# Shark.net
KiCad netlist of a schematic drawn in Altium Designer
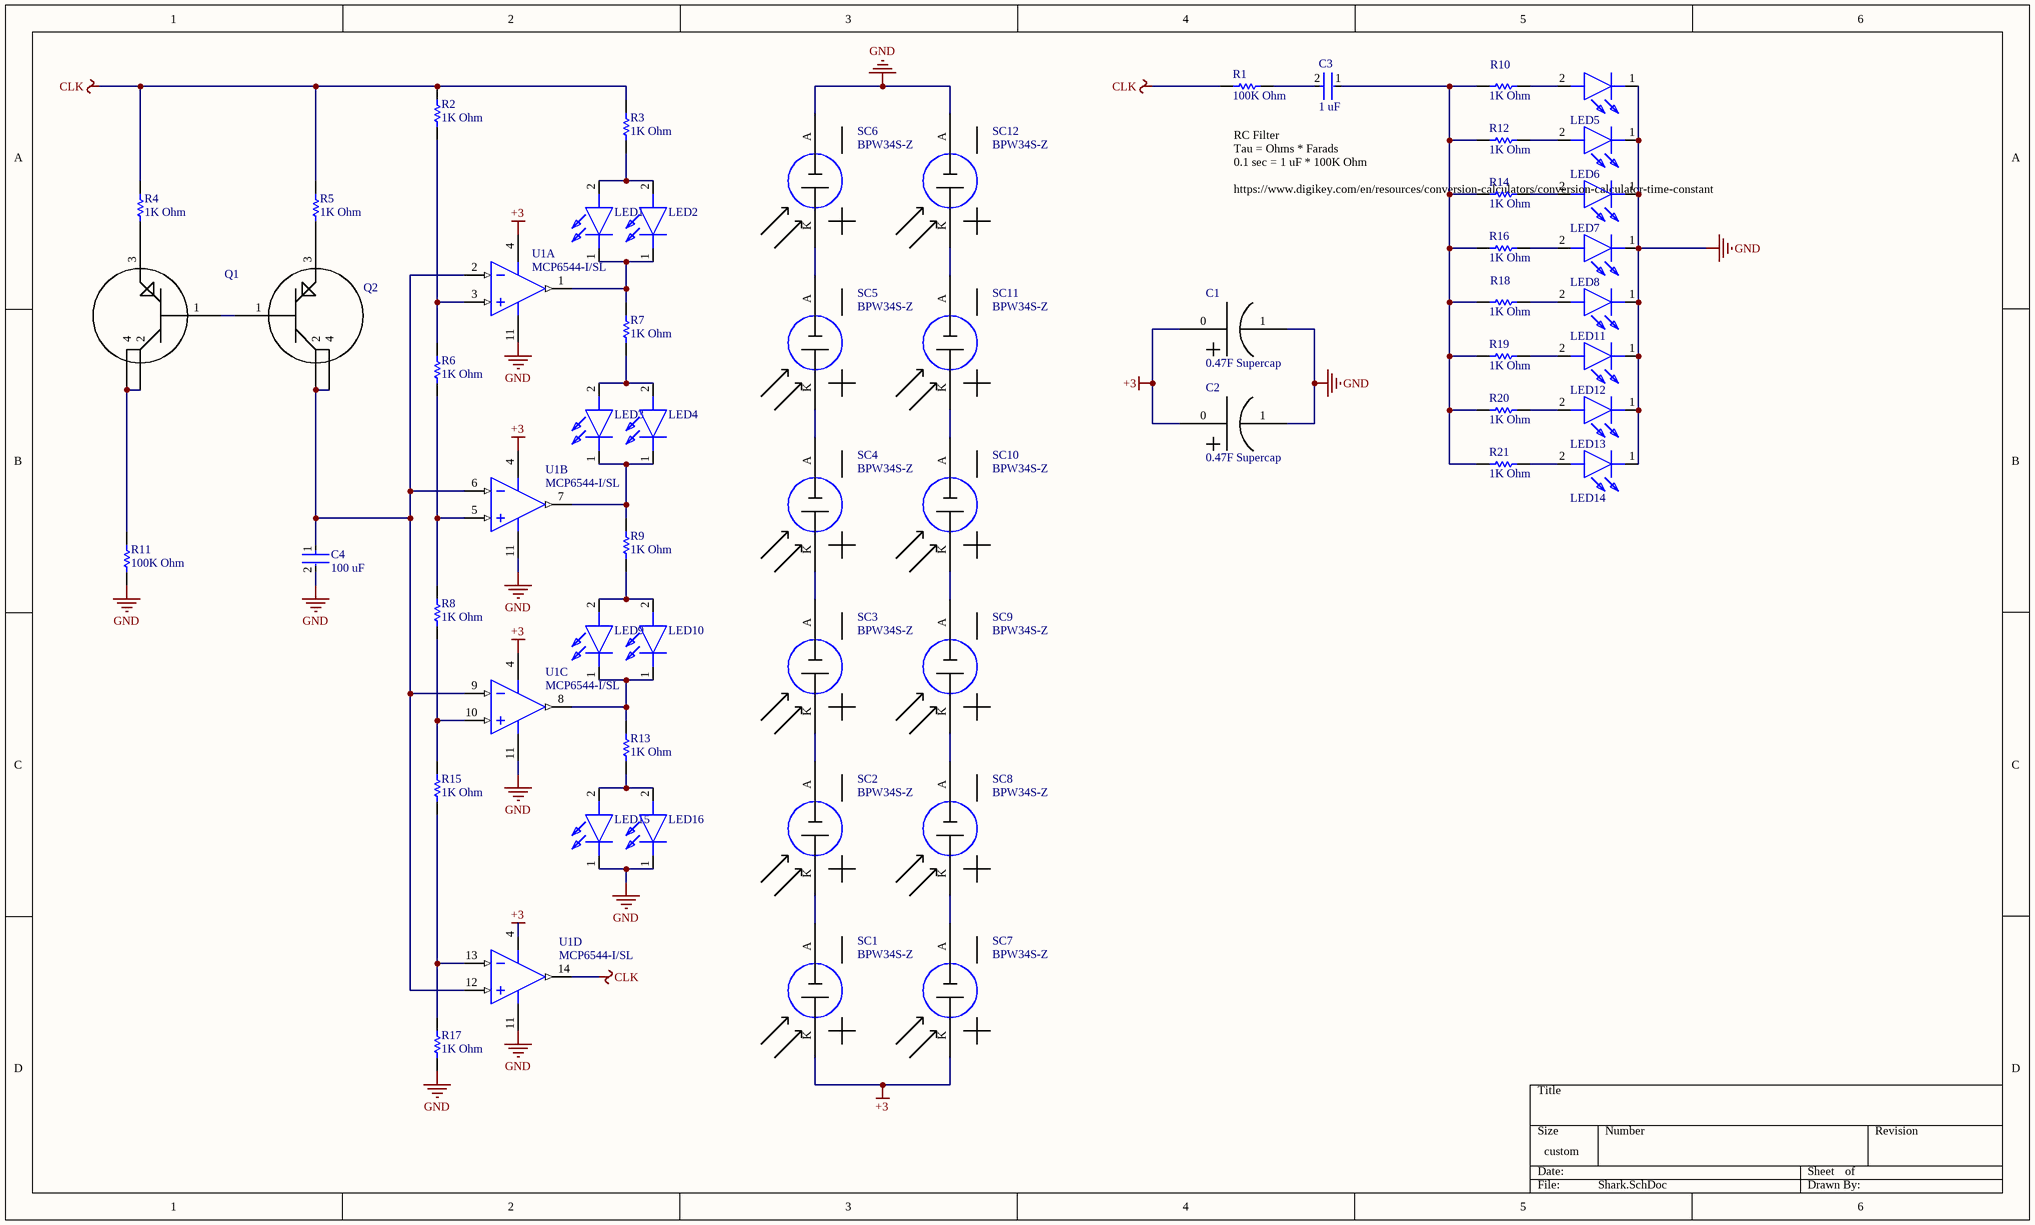
[diagram p0: Shark.SchDoc]

(export (version "E")
  (design (tool "Eeschema 10.0.6"))
  (components
    (comp (ref "C1")
      (value "0.47F Supercap")
      (footprint "JUMT1474MED")
      (description "Cap Supercap 0.47F 2.7V 20% (6.3 X 9mm) Radial 2.5mm 4 Ohm 1000h 70C Bulk Automotive")
      (fields
        (field (name "MANUFACTURER") "Nichicon")
        (field (name "MANUFACTURER PART NUMBER") "JUMT1474MED")
      )
      (libsource (lib "Schlib1") (part "JUMT1474MED"))
    )
    (comp (ref "C2")
      (value "0.47F Supercap")
      (footprint "JUMT1474MED")
      (description "Cap Supercap 0.47F 2.7V 20% (6.3 X 9mm) Radial 2.5mm 4 Ohm 1000h 70C Bulk Automotive")
      (fields
        (field (name "MANUFACTURER") "Nichicon")
        (field (name "MANUFACTURER PART NUMBER") "JUMT1474MED")
      )
      (libsource (lib "Schlib1") (part "JUMT1474MED"))
    )
    (comp (ref "C3")
      (value "1 uF")
      (footprint "FP-1812-L_4_5_0_3-W_3_2_0-IPC_B")
      (description "General Purpose Ceramic Capacitor, 1812, 1uF, 10%, X7R, 15%, 100V")
      (fields (field (name "TOLERANCE") "10%") (field (name "VOLTAGE") "100V"))
      (libsource (lib "Altium Content Vault") (part "f23184f103b6ebe33a8c269c53dcba6"))
    )
    (comp (ref "C4")
      (value "100 uF")
      (footprint "FP-GRM21B-0_2-e0_2_0_7-IPC_A")
      (description "Chip Multilayer Ceramic Capacitors for General Purpose, 0805, 100uF, X5R, 15%, 20%, 6.3V")
      (fields (field (name "TOLERANCE") "20%"))
      (libsource (lib "Altium Content Vault") (part "b4654b650e69147ec39a6b967a45e02"))
    )
    (comp (ref "LED1")
      (value "CSL1104WBBW1")
      (footprint "CSL1104WBBW1")
      (description "LED")
      (libsource (lib "Schlib1") (part "CSL1104WBBW1"))
    )
    (comp (ref "LED2")
      (value "CSL1104WBBW1")
      (footprint "CSL1104WBBW1")
      (description "LED")
      (libsource (lib "Schlib1") (part "CSL1104WBBW1"))
    )
    (comp (ref "LED3")
      (value "CSL1104WBBW1")
      (footprint "CSL1104WBBW1")
      (description "LED")
      (libsource (lib "Schlib1") (part "CSL1104WBBW1"))
    )
    (comp (ref "LED4")
      (value "CSL1104WBBW1")
      (footprint "CSL1104WBBW1")
      (description "LED")
      (libsource (lib "Schlib1") (part "CSL1104WBBW1"))
    )
    (comp (ref "LED5")
      (value "CSL1104WBBW1")
      (footprint "CSL1104WBBW1")
      (description "LED")
      (libsource (lib "Schlib1") (part "CSL1104WBBW1"))
    )
    (comp (ref "LED6")
      (value "CSL1104WBBW1")
      (footprint "CSL1104WBBW1")
      (description "LED")
      (libsource (lib "Schlib1") (part "CSL1104WBBW1"))
    )
    (comp (ref "LED7")
      (value "CSL1104WBBW1")
      (footprint "CSL1104WBBW1")
      (description "LED")
      (libsource (lib "Schlib1") (part "CSL1104WBBW1"))
    )
    (comp (ref "LED8")
      (value "CSL1104WBBW1")
      (footprint "CSL1104WBBW1")
      (description "LED")
      (libsource (lib "Schlib1") (part "CSL1104WBBW1"))
    )
    (comp (ref "LED9")
      (value "CSL1104WBBW1")
      (footprint "CSL1104WBBW1")
      (description "LED")
      (libsource (lib "Schlib1") (part "CSL1104WBBW1"))
    )
    (comp (ref "LED10")
      (value "CSL1104WBBW1")
      (footprint "CSL1104WBBW1")
      (description "LED")
      (libsource (lib "Schlib1") (part "CSL1104WBBW1"))
    )
    (comp (ref "LED11")
      (value "CSL1104WBBW1")
      (footprint "CSL1104WBBW1")
      (description "LED")
      (libsource (lib "Schlib1") (part "CSL1104WBBW1"))
    )
    (comp (ref "LED12")
      (value "CSL1104WBBW1")
      (footprint "CSL1104WBBW1")
      (description "LED")
      (libsource (lib "Schlib1") (part "CSL1104WBBW1"))
    )
    (comp (ref "LED13")
      (value "CSL1104WBBW1")
      (footprint "CSL1104WBBW1")
      (description "LED")
      (libsource (lib "Schlib1") (part "CSL1104WBBW1"))
    )
    (comp (ref "LED14")
      (value "CSL1104WBBW1")
      (footprint "CSL1104WBBW1")
      (description "LED")
      (libsource (lib "Schlib1") (part "CSL1104WBBW1"))
    )
    (comp (ref "LED15")
      (value "CSL1104WBBW1")
      (footprint "CSL1104WBBW1")
      (description "LED")
      (libsource (lib "Schlib1") (part "CSL1104WBBW1"))
    )
    (comp (ref "LED16")
      (value "CSL1104WBBW1")
      (footprint "CSL1104WBBW1")
      (description "LED")
      (libsource (lib "Schlib1") (part "CSL1104WBBW1"))
    )
    (comp (ref "Q1")
      (value "PZT3906T1G")
      (footprint "PZT3906T1G")
      (description "Transistor Gp Bjt PNP 40V 200MA 4-PIN SOT-223 T/r")
      (fields (field (name "MANUFACTURER") "ON Semiconductor"))
      (libsource (lib "Schlib1") (part "PZT3906T1G"))
    )
    (comp (ref "Q2")
      (value "PZT3906T1G")
      (footprint "PZT3906T1G")
      (description "Transistor Gp Bjt PNP 40V 200MA 4-PIN SOT-223 T/r")
      (fields (field (name "MANUFACTURER") "ON Semiconductor"))
      (libsource (lib "Schlib1") (part "PZT3906T1G"))
    )
    (comp (ref "R1")
      (value "100K Ohm")
      (footprint "RESC2013X60X35ML10T20")
      (description "Chip Resistor, 100 KOhm, +/- 1%, 0.125 W, -55 to 155 degC, 0805 (2012 Metric), RoHS, Tape and Reel")
      (fields (field (name "MANUFACTURER") "Yageo") (field (name "TOLERANCE") "1%"))
      (libsource (lib "Altium Content Vault") (part "RES-2"))
    )
    (comp (ref "R2")
      (value "1K Ohm")
      (footprint "RESC2013X50X30NL20T20")
      (fields (field (name "PART NUMBER") "CRCW08051K00FKEA") (field (name "MANUFACTURER") "Vishay Dale"))
      (libsource (lib "Altium Content Vault") (part "RES"))
    )
    (comp (ref "R3")
      (value "1K Ohm")
      (footprint "RESC2013X50X30NL20T20")
      (fields (field (name "PART NUMBER") "CRCW08051K00FKEA") (field (name "MANUFACTURER") "Vishay Dale"))
      (libsource (lib "Altium Content Vault") (part "RES"))
    )
    (comp (ref "R4")
      (value "1K Ohm")
      (footprint "RESC2013X50X30NL20T20")
      (fields (field (name "PART NUMBER") "CRCW08051K00FKEA") (field (name "MANUFACTURER") "Vishay Dale"))
      (libsource (lib "Altium Content Vault") (part "RES"))
    )
    (comp (ref "R5")
      (value "1K Ohm")
      (footprint "RESC2013X50X30NL20T20")
      (fields (field (name "PART NUMBER") "CRCW08051K00FKEA") (field (name "MANUFACTURER") "Vishay Dale"))
      (libsource (lib "Altium Content Vault") (part "RES"))
    )
    (comp (ref "R6")
      (value "1K Ohm")
      (footprint "RESC2013X50X30NL20T20")
      (fields (field (name "PART NUMBER") "CRCW08051K00FKEA") (field (name "MANUFACTURER") "Vishay Dale"))
      (libsource (lib "Altium Content Vault") (part "RES"))
    )
    (comp (ref "R7")
      (value "1K Ohm")
      (footprint "RESC2013X50X30NL20T20")
      (fields (field (name "PART NUMBER") "CRCW08051K00FKEA") (field (name "MANUFACTURER") "Vishay Dale"))
      (libsource (lib "Altium Content Vault") (part "RES"))
    )
    (comp (ref "R8")
      (value "1K Ohm")
      (footprint "RESC2013X50X30NL20T20")
      (fields (field (name "PART NUMBER") "CRCW08051K00FKEA") (field (name "MANUFACTURER") "Vishay Dale"))
      (libsource (lib "Altium Content Vault") (part "RES"))
    )
    (comp (ref "R9")
      (value "1K Ohm")
      (footprint "RESC2013X50X30NL20T20")
      (fields (field (name "PART NUMBER") "CRCW08051K00FKEA") (field (name "MANUFACTURER") "Vishay Dale"))
      (libsource (lib "Altium Content Vault") (part "RES"))
    )
    (comp (ref "R10")
      (value "1K Ohm")
      (footprint "RESC2013X50X30NL20T20")
      (fields (field (name "PART NUMBER") "CRCW08051K00FKEA") (field (name "MANUFACTURER") "Vishay Dale"))
      (libsource (lib "Altium Content Vault") (part "RES"))
    )
    (comp (ref "R11")
      (value "100K Ohm")
      (footprint "RESC2013X60X35ML10T20")
      (description "Chip Resistor, 100 KOhm, +/- 1%, 0.125 W, -55 to 155 degC, 0805 (2012 Metric), RoHS, Tape and Reel")
      (fields (field (name "MANUFACTURER") "Yageo") (field (name "TOLERANCE") "1%"))
      (libsource (lib "Altium Content Vault") (part "RES-2"))
    )
    (comp (ref "R12")
      (value "1K Ohm")
      (footprint "RESC2013X50X30NL20T20")
      (fields (field (name "PART NUMBER") "CRCW08051K00FKEA") (field (name "MANUFACTURER") "Vishay Dale"))
      (libsource (lib "Altium Content Vault") (part "RES"))
    )
    (comp (ref "R13")
      (value "1K Ohm")
      (footprint "RESC2013X50X30NL20T20")
      (fields (field (name "PART NUMBER") "CRCW08051K00FKEA") (field (name "MANUFACTURER") "Vishay Dale"))
      (libsource (lib "Altium Content Vault") (part "RES"))
    )
    (comp (ref "R14")
      (value "1K Ohm")
      (footprint "RESC2013X50X30NL20T20")
      (fields (field (name "PART NUMBER") "CRCW08051K00FKEA") (field (name "MANUFACTURER") "Vishay Dale"))
      (libsource (lib "Altium Content Vault") (part "RES"))
    )
    (comp (ref "R15")
      (value "1K Ohm")
      (footprint "RESC2013X50X30NL20T20")
      (fields (field (name "PART NUMBER") "CRCW08051K00FKEA") (field (name "MANUFACTURER") "Vishay Dale"))
      (libsource (lib "Altium Content Vault") (part "RES"))
    )
    (comp (ref "R16")
      (value "1K Ohm")
      (footprint "RESC2013X50X30NL20T20")
      (fields (field (name "PART NUMBER") "CRCW08051K00FKEA") (field (name "MANUFACTURER") "Vishay Dale"))
      (libsource (lib "Altium Content Vault") (part "RES"))
    )
    (comp (ref "R17")
      (value "1K Ohm")
      (footprint "RESC2013X50X30NL20T20")
      (fields (field (name "PART NUMBER") "CRCW08051K00FKEA") (field (name "MANUFACTURER") "Vishay Dale"))
      (libsource (lib "Altium Content Vault") (part "RES"))
    )
    (comp (ref "R18")
      (value "1K Ohm")
      (footprint "RESC2013X50X30NL20T20")
      (fields (field (name "PART NUMBER") "CRCW08051K00FKEA") (field (name "MANUFACTURER") "Vishay Dale"))
      (libsource (lib "Altium Content Vault") (part "RES"))
    )
    (comp (ref "R19")
      (value "1K Ohm")
      (footprint "RESC2013X50X30NL20T20")
      (fields (field (name "PART NUMBER") "CRCW08051K00FKEA") (field (name "MANUFACTURER") "Vishay Dale"))
      (libsource (lib "Altium Content Vault") (part "RES"))
    )
    (comp (ref "R20")
      (value "1K Ohm")
      (footprint "RESC2013X50X30NL20T20")
      (fields (field (name "PART NUMBER") "CRCW08051K00FKEA") (field (name "MANUFACTURER") "Vishay Dale"))
      (libsource (lib "Altium Content Vault") (part "RES"))
    )
    (comp (ref "R21")
      (value "1K Ohm")
      (footprint "RESC2013X50X30NL20T20")
      (fields (field (name "PART NUMBER") "CRCW08051K00FKEA") (field (name "MANUFACTURER") "Vishay Dale"))
      (libsource (lib "Altium Content Vault") (part "RES"))
    )
    (comp (ref "SC1")
      (value "BPW34S-Z")
      (footprint "BPW34S-Z")
      (description "Photodiode PIN Chip 850nm 0.62A/W Sensitivity Automotive 2-Pin DIL SMT")
      (fields (field (name "MANUFACTURER") "Osram Opto"))
      (libsource (lib "Schlib1") (part "BPW34S-Z"))
    )
    (comp (ref "SC2")
      (value "BPW34S-Z")
      (footprint "BPW34S-Z")
      (description "Photodiode PIN Chip 850nm 0.62A/W Sensitivity Automotive 2-Pin DIL SMT")
      (fields (field (name "MANUFACTURER") "Osram Opto"))
      (libsource (lib "Schlib1") (part "BPW34S-Z"))
    )
    (comp (ref "SC3")
      (value "BPW34S-Z")
      (footprint "BPW34S-Z")
      (description "Photodiode PIN Chip 850nm 0.62A/W Sensitivity Automotive 2-Pin DIL SMT")
      (fields (field (name "MANUFACTURER") "Osram Opto"))
      (libsource (lib "Schlib1") (part "BPW34S-Z"))
    )
    (comp (ref "SC4")
      (value "BPW34S-Z")
      (footprint "BPW34S-Z")
      (description "Photodiode PIN Chip 850nm 0.62A/W Sensitivity Automotive 2-Pin DIL SMT")
      (fields (field (name "MANUFACTURER") "Osram Opto"))
      (libsource (lib "Schlib1") (part "BPW34S-Z"))
    )
    (comp (ref "SC5")
      (value "BPW34S-Z")
      (footprint "BPW34S-Z")
      (description "Photodiode PIN Chip 850nm 0.62A/W Sensitivity Automotive 2-Pin DIL SMT")
      (fields (field (name "MANUFACTURER") "Osram Opto"))
      (libsource (lib "Schlib1") (part "BPW34S-Z"))
    )
    (comp (ref "SC6")
      (value "BPW34S-Z")
      (footprint "BPW34S-Z")
      (description "Photodiode PIN Chip 850nm 0.62A/W Sensitivity Automotive 2-Pin DIL SMT")
      (fields (field (name "MANUFACTURER") "Osram Opto"))
      (libsource (lib "Schlib1") (part "BPW34S-Z"))
    )
    (comp (ref "SC7")
      (value "BPW34S-Z")
      (footprint "BPW34S-Z")
      (description "Photodiode PIN Chip 850nm 0.62A/W Sensitivity Automotive 2-Pin DIL SMT")
      (fields (field (name "MANUFACTURER") "Osram Opto"))
      (libsource (lib "Schlib1") (part "BPW34S-Z"))
    )
    (comp (ref "SC8")
      (value "BPW34S-Z")
      (footprint "BPW34S-Z")
      (description "Photodiode PIN Chip 850nm 0.62A/W Sensitivity Automotive 2-Pin DIL SMT")
      (fields (field (name "MANUFACTURER") "Osram Opto"))
      (libsource (lib "Schlib1") (part "BPW34S-Z"))
    )
    (comp (ref "SC9")
      (value "BPW34S-Z")
      (footprint "BPW34S-Z")
      (description "Photodiode PIN Chip 850nm 0.62A/W Sensitivity Automotive 2-Pin DIL SMT")
      (fields (field (name "MANUFACTURER") "Osram Opto"))
      (libsource (lib "Schlib1") (part "BPW34S-Z"))
    )
    (comp (ref "SC10")
      (value "BPW34S-Z")
      (footprint "BPW34S-Z")
      (description "Photodiode PIN Chip 850nm 0.62A/W Sensitivity Automotive 2-Pin DIL SMT")
      (fields (field (name "MANUFACTURER") "Osram Opto"))
      (libsource (lib "Schlib1") (part "BPW34S-Z"))
    )
    (comp (ref "SC11")
      (value "BPW34S-Z")
      (footprint "BPW34S-Z")
      (description "Photodiode PIN Chip 850nm 0.62A/W Sensitivity Automotive 2-Pin DIL SMT")
      (fields (field (name "MANUFACTURER") "Osram Opto"))
      (libsource (lib "Schlib1") (part "BPW34S-Z"))
    )
    (comp (ref "SC12")
      (value "BPW34S-Z")
      (footprint "BPW34S-Z")
      (description "Photodiode PIN Chip 850nm 0.62A/W Sensitivity Automotive 2-Pin DIL SMT")
      (fields (field (name "MANUFACTURER") "Osram Opto"))
      (libsource (lib "Schlib1") (part "BPW34S-Z"))
    )
    (comp (ref "U1")
      (value "MCP6544-I/SL")
      (footprint "SOIC-SL14_N")
      (description "None")
      (libsource (lib "Altium Content Vault") (part "LO-COMP-MCP6544-IL14"))
    )
  )
  (nets
    (net (code "1") (name "+3") (class "Default")
      (node (ref "C1") (pin "0") (pinfunction "0_0") (pintype "passive"))
      (node (ref "C2") (pin "0") (pinfunction "0_0") (pintype "passive"))
      (node (ref "SC1") (pin "K") (pinfunction "Cathode_K") (pintype "passive"))
      (node (ref "SC7") (pin "K") (pinfunction "Cathode_K") (pintype "passive"))
      (node (ref "U1") (pin "4") (pinfunction "VDD_4") (pintype "power_in"))
    )
    (net (code "2") (name "CLK") (class "Default")
      (node (ref "R1") (pin "2") (pinfunction "2_2") (pintype "passive"))
      (node (ref "R2") (pin "2") (pinfunction "2_2") (pintype "passive"))
      (node (ref "R3") (pin "2") (pinfunction "2_2") (pintype "passive"))
      (node (ref "R4") (pin "2") (pinfunction "2_2") (pintype "passive"))
      (node (ref "R5") (pin "2") (pinfunction "2_2") (pintype "passive"))
      (node (ref "U1") (pin "14") (pinfunction "OUTD_14") (pintype "output"))
    )
    (net (code "3") (name "GND") (class "Default")
      (node (ref "C1") (pin "1") (pinfunction "1_1") (pintype "passive"))
      (node (ref "C2") (pin "1") (pinfunction "1_1") (pintype "passive"))
      (node (ref "C4") (pin "2") (pinfunction "2_2") (pintype "passive"))
      (node (ref "LED11") (pin "1") (pinfunction "K_1") (pintype "passive"))
      (node (ref "LED12") (pin "1") (pinfunction "K_1") (pintype "passive"))
      (node (ref "LED13") (pin "1") (pinfunction "K_1") (pintype "passive"))
      (node (ref "LED14") (pin "1") (pinfunction "K_1") (pintype "passive"))
      (node (ref "LED15") (pin "1") (pinfunction "K_1") (pintype "passive"))
      (node (ref "LED16") (pin "1") (pinfunction "K_1") (pintype "passive"))
      (node (ref "LED5") (pin "1") (pinfunction "K_1") (pintype "passive"))
      (node (ref "LED6") (pin "1") (pinfunction "K_1") (pintype "passive"))
      (node (ref "LED7") (pin "1") (pinfunction "K_1") (pintype "passive"))
      (node (ref "LED8") (pin "1") (pinfunction "K_1") (pintype "passive"))
      (node (ref "R11") (pin "1") (pinfunction "1_1") (pintype "passive"))
      (node (ref "R17") (pin "1") (pinfunction "1_1") (pintype "passive"))
      (node (ref "SC12") (pin "A") (pinfunction "Anode_A") (pintype "passive"))
      (node (ref "SC6") (pin "A") (pinfunction "Anode_A") (pintype "passive"))
      (node (ref "U1") (pin "11") (pinfunction "VSS_11") (pintype "power_in"))
    )
    (net (code "4") (name "Net-(C3-Pad1)") (class "Default")
      (node (ref "C3") (pin "1") (pinfunction "1_1") (pintype "passive"))
      (node (ref "R10") (pin "2") (pinfunction "2_2") (pintype "passive"))
      (node (ref "R12") (pin "2") (pinfunction "2_2") (pintype "passive"))
      (node (ref "R14") (pin "2") (pinfunction "2_2") (pintype "passive"))
      (node (ref "R16") (pin "2") (pinfunction "2_2") (pintype "passive"))
      (node (ref "R18") (pin "2") (pinfunction "2_2") (pintype "passive"))
      (node (ref "R19") (pin "2") (pinfunction "2_2") (pintype "passive"))
      (node (ref "R20") (pin "2") (pinfunction "2_2") (pintype "passive"))
      (node (ref "R21") (pin "2") (pinfunction "2_2") (pintype "passive"))
    )
    (net (code "5") (name "Net-(C3-Pad2)") (class "Default")
      (node (ref "C3") (pin "2") (pinfunction "2_2") (pintype "passive"))
      (node (ref "R1") (pin "1") (pinfunction "1_1") (pintype "passive"))
    )
    (net (code "6") (name "Net-(LED1-A)") (class "Default")
      (node (ref "LED1") (pin "2") (pinfunction "A_2") (pintype "passive"))
      (node (ref "LED2") (pin "2") (pinfunction "A_2") (pintype "passive"))
      (node (ref "R3") (pin "1") (pinfunction "1_1") (pintype "passive"))
    )
    (net (code "7") (name "Net-(LED1-K)") (class "Default")
      (node (ref "LED1") (pin "1") (pinfunction "K_1") (pintype "passive"))
      (node (ref "LED2") (pin "1") (pinfunction "K_1") (pintype "passive"))
      (node (ref "R7") (pin "2") (pinfunction "2_2") (pintype "passive"))
      (node (ref "U1") (pin "1") (pinfunction "OUTA_1") (pintype "output"))
    )
    (net (code "8") (name "Net-(LED3-A)") (class "Default")
      (node (ref "LED3") (pin "2") (pinfunction "A_2") (pintype "passive"))
      (node (ref "LED4") (pin "2") (pinfunction "A_2") (pintype "passive"))
      (node (ref "R7") (pin "1") (pinfunction "1_1") (pintype "passive"))
    )
    (net (code "9") (name "Net-(LED3-K)") (class "Default")
      (node (ref "LED3") (pin "1") (pinfunction "K_1") (pintype "passive"))
      (node (ref "LED4") (pin "1") (pinfunction "K_1") (pintype "passive"))
      (node (ref "R9") (pin "2") (pinfunction "2_2") (pintype "passive"))
      (node (ref "U1") (pin "7") (pinfunction "OUTB_7") (pintype "output"))
    )
    (net (code "10") (name "Net-(LED5-A)") (class "Default")
      (node (ref "LED5") (pin "2") (pinfunction "A_2") (pintype "passive"))
      (node (ref "R10") (pin "1") (pinfunction "1_1") (pintype "passive"))
    )
    (net (code "11") (name "Net-(LED6-A)") (class "Default")
      (node (ref "LED6") (pin "2") (pinfunction "A_2") (pintype "passive"))
      (node (ref "R12") (pin "1") (pinfunction "1_1") (pintype "passive"))
    )
    (net (code "12") (name "Net-(LED7-A)") (class "Default")
      (node (ref "LED7") (pin "2") (pinfunction "A_2") (pintype "passive"))
      (node (ref "R14") (pin "1") (pinfunction "1_1") (pintype "passive"))
    )
    (net (code "13") (name "Net-(LED8-A)") (class "Default")
      (node (ref "LED8") (pin "2") (pinfunction "A_2") (pintype "passive"))
      (node (ref "R16") (pin "1") (pinfunction "1_1") (pintype "passive"))
    )
    (net (code "14") (name "Net-(LED10-A)") (class "Default")
      (node (ref "LED10") (pin "2") (pinfunction "A_2") (pintype "passive"))
      (node (ref "LED9") (pin "2") (pinfunction "A_2") (pintype "passive"))
      (node (ref "R9") (pin "1") (pinfunction "1_1") (pintype "passive"))
    )
    (net (code "15") (name "Net-(LED10-K)") (class "Default")
      (node (ref "LED10") (pin "1") (pinfunction "K_1") (pintype "passive"))
      (node (ref "LED9") (pin "1") (pinfunction "K_1") (pintype "passive"))
      (node (ref "R13") (pin "2") (pinfunction "2_2") (pintype "passive"))
      (node (ref "U1") (pin "8") (pinfunction "OUTC_8") (pintype "output"))
    )
    (net (code "16") (name "Net-(LED11-A)") (class "Default")
      (node (ref "LED11") (pin "2") (pinfunction "A_2") (pintype "passive"))
      (node (ref "R18") (pin "1") (pinfunction "1_1") (pintype "passive"))
    )
    (net (code "17") (name "Net-(LED12-A)") (class "Default")
      (node (ref "LED12") (pin "2") (pinfunction "A_2") (pintype "passive"))
      (node (ref "R19") (pin "1") (pinfunction "1_1") (pintype "passive"))
    )
    (net (code "18") (name "Net-(LED13-A)") (class "Default")
      (node (ref "LED13") (pin "2") (pinfunction "A_2") (pintype "passive"))
      (node (ref "R20") (pin "1") (pinfunction "1_1") (pintype "passive"))
    )
    (net (code "19") (name "Net-(LED14-A)") (class "Default")
      (node (ref "LED14") (pin "2") (pinfunction "A_2") (pintype "passive"))
      (node (ref "R21") (pin "1") (pinfunction "1_1") (pintype "passive"))
    )
    (net (code "20") (name "Net-(LED15-A)") (class "Default")
      (node (ref "LED15") (pin "2") (pinfunction "A_2") (pintype "passive"))
      (node (ref "LED16") (pin "2") (pinfunction "A_2") (pintype "passive"))
      (node (ref "R13") (pin "1") (pinfunction "1_1") (pintype "passive"))
    )
    (net (code "21") (name "Net-(Q1-Pad1)") (class "Default")
      (node (ref "Q1") (pin "1") (pinfunction "1_1") (pintype "passive"))
      (node (ref "Q2") (pin "1") (pinfunction "1_1") (pintype "passive"))
    )
    (net (code "22") (name "Net-(Q1-Pad2)") (class "Default")
      (node (ref "Q1") (pin "2") (pinfunction "2_2") (pintype "passive"))
      (node (ref "Q1") (pin "4") (pinfunction "4_4") (pintype "passive"))
      (node (ref "R11") (pin "2") (pinfunction "2_2") (pintype "passive"))
    )
    (net (code "23") (name "Net-(Q1-Pad3)") (class "Default")
      (node (ref "Q1") (pin "3") (pinfunction "3_3") (pintype "passive"))
      (node (ref "R4") (pin "1") (pinfunction "1_1") (pintype "passive"))
    )
    (net (code "24") (name "Net-(Q2-Pad3)") (class "Default")
      (node (ref "Q2") (pin "3") (pinfunction "3_3") (pintype "passive"))
      (node (ref "R5") (pin "1") (pinfunction "1_1") (pintype "passive"))
    )
    (net (code "25") (name "Net-(SC1-Anode)") (class "Default")
      (node (ref "SC1") (pin "A") (pinfunction "Anode_A") (pintype "passive"))
      (node (ref "SC2") (pin "K") (pinfunction "Cathode_K") (pintype "passive"))
    )
    (net (code "26") (name "Net-(SC2-Anode)") (class "Default")
      (node (ref "SC2") (pin "A") (pinfunction "Anode_A") (pintype "passive"))
      (node (ref "SC3") (pin "K") (pinfunction "Cathode_K") (pintype "passive"))
    )
    (net (code "27") (name "Net-(SC3-Anode)") (class "Default")
      (node (ref "SC3") (pin "A") (pinfunction "Anode_A") (pintype "passive"))
      (node (ref "SC4") (pin "K") (pinfunction "Cathode_K") (pintype "passive"))
    )
    (net (code "28") (name "Net-(SC4-Anode)") (class "Default")
      (node (ref "SC4") (pin "A") (pinfunction "Anode_A") (pintype "passive"))
      (node (ref "SC5") (pin "K") (pinfunction "Cathode_K") (pintype "passive"))
    )
    (net (code "29") (name "Net-(SC5-Anode)") (class "Default")
      (node (ref "SC5") (pin "A") (pinfunction "Anode_A") (pintype "passive"))
      (node (ref "SC6") (pin "K") (pinfunction "Cathode_K") (pintype "passive"))
    )
    (net (code "30") (name "Net-(SC7-Anode)") (class "Default")
      (node (ref "SC7") (pin "A") (pinfunction "Anode_A") (pintype "passive"))
      (node (ref "SC8") (pin "K") (pinfunction "Cathode_K") (pintype "passive"))
    )
    (net (code "31") (name "Net-(SC8-Anode)") (class "Default")
      (node (ref "SC8") (pin "A") (pinfunction "Anode_A") (pintype "passive"))
      (node (ref "SC9") (pin "K") (pinfunction "Cathode_K") (pintype "passive"))
    )
    (net (code "32") (name "Net-(SC10-Anode)") (class "Default")
      (node (ref "SC10") (pin "A") (pinfunction "Anode_A") (pintype "passive"))
      (node (ref "SC11") (pin "K") (pinfunction "Cathode_K") (pintype "passive"))
    )
    (net (code "33") (name "Net-(SC10-Cathode)") (class "Default")
      (node (ref "SC10") (pin "K") (pinfunction "Cathode_K") (pintype "passive"))
      (node (ref "SC9") (pin "A") (pinfunction "Anode_A") (pintype "passive"))
    )
    (net (code "34") (name "Net-(SC11-Anode)") (class "Default")
      (node (ref "SC11") (pin "A") (pinfunction "Anode_A") (pintype "passive"))
      (node (ref "SC12") (pin "K") (pinfunction "Cathode_K") (pintype "passive"))
    )
    (net (code "35") (name "Net-(U1A-VINA+)") (class "Default")
      (node (ref "R2") (pin "1") (pinfunction "1_1") (pintype "passive"))
      (node (ref "R6") (pin "2") (pinfunction "2_2") (pintype "passive"))
      (node (ref "U1") (pin "3") (pinfunction "VINA+_3") (pintype "input"))
    )
    (net (code "36") (name "Net-(U1A-VINA-)") (class "Default")
      (node (ref "C4") (pin "1") (pinfunction "1_1") (pintype "passive"))
      (node (ref "Q2") (pin "2") (pinfunction "2_2") (pintype "passive"))
      (node (ref "Q2") (pin "4") (pinfunction "4_4") (pintype "passive"))
      (node (ref "U1") (pin "12") (pinfunction "VIND+_12") (pintype "input"))
      (node (ref "U1") (pin "2") (pinfunction "VINA-_2") (pintype "input"))
      (node (ref "U1") (pin "6") (pinfunction "VINB-_6") (pintype "input"))
      (node (ref "U1") (pin "9") (pinfunction "VINC-_9") (pintype "input"))
    )
    (net (code "37") (name "Net-(U1B-VINB+)") (class "Default")
      (node (ref "R6") (pin "1") (pinfunction "1_1") (pintype "passive"))
      (node (ref "R8") (pin "2") (pinfunction "2_2") (pintype "passive"))
      (node (ref "U1") (pin "5") (pinfunction "VINB+_5") (pintype "input"))
    )
    (net (code "38") (name "Net-(U1C-VINC+)") (class "Default")
      (node (ref "R15") (pin "2") (pinfunction "2_2") (pintype "passive"))
      (node (ref "R8") (pin "1") (pinfunction "1_1") (pintype "passive"))
      (node (ref "U1") (pin "10") (pinfunction "VINC+_10") (pintype "input"))
    )
    (net (code "39") (name "Net-(U1D-VIND-)") (class "Default")
      (node (ref "R15") (pin "1") (pinfunction "1_1") (pintype "passive"))
      (node (ref "R17") (pin "2") (pinfunction "2_2") (pintype "passive"))
      (node (ref "U1") (pin "13") (pinfunction "VIND-_13") (pintype "input"))
    )
  )
)
